# DAC_AFE.net
KiCad netlist of a schematic drawn in Altium Designer
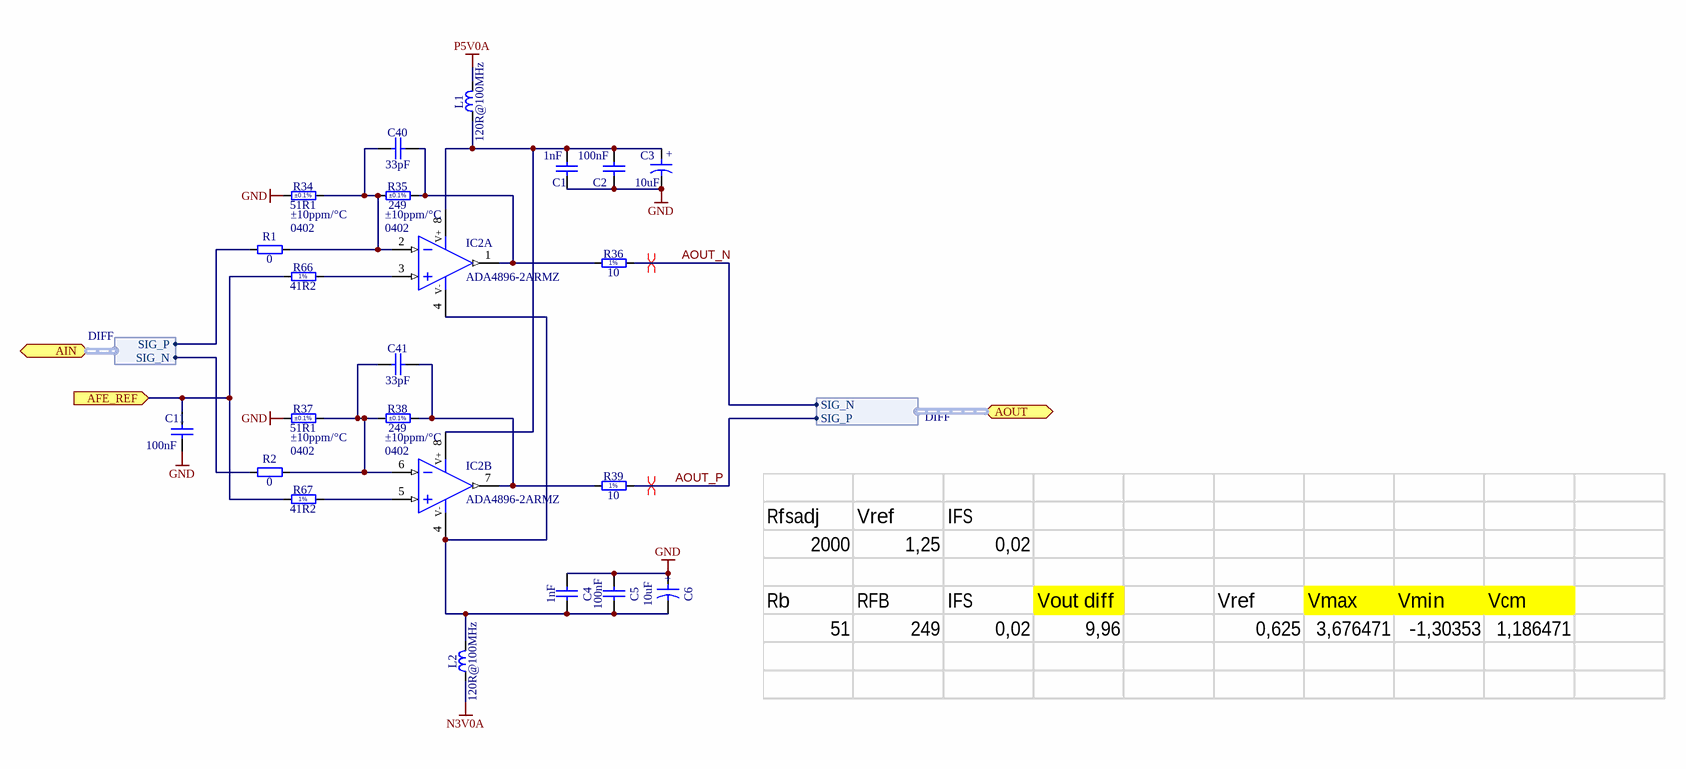
[diagram p0: DAC_AFE.SchDoc]

(export (version "E")
  (design (tool "Eeschema 10.0.6"))
  (components
    (comp (ref "C1")
      (value "1nF")
      (footprint "CAPC0603X33N")
      (description "Non-polarised capacitor")
      (fields
        (field (name "PART NUMBER") "CC0201_1NF_16V_10%_X5R")
        (field (name "VOLTAGE") "16V")
        (field (name "AUTHOR") "CERN DEM JLC")
      )
      (libsource (lib "Capacitors") (part "Capacitor - non polarized"))
    )
    (comp (ref "C2")
      (value "100nF")
      (footprint "CAPC0603X33N")
      (description "Non-polarised capacitor")
      (fields
        (field (name "PART NUMBER") "CC0201_100NF_6.3V_10%_X5R")
        (field (name "VOLTAGE") "6.3V")
        (field (name "AUTHOR") "CERN DEM JLC")
      )
      (libsource (lib "Capacitors") (part "Capacitor - non polarized"))
    )
    (comp (ref "C3")
      (value "10uF")
      (footprint "CAPMP3216X180N")
      (description "Polarised capacitor")
      (fields
        (field (name "PART NUMBER") "CTE3216-18_10UF_10V_10%_LESR1800")
        (field (name "VOLTAGE") "10V")
        (field (name "AUTHOR") "CERN DEM JLC")
      )
      (libsource (lib "Capacitors") (part "Capacitor - polarized"))
    )
    (comp (ref "C4")
      (value "1nF")
      (footprint "CAPC0603X33N")
      (description "Non-polarised capacitor")
      (fields
        (field (name "PART NUMBER") "CC0201_1NF_16V_10%_X5R")
        (field (name "VOLTAGE") "16V")
        (field (name "AUTHOR") "CERN DEM JLC")
      )
      (libsource (lib "Capacitors") (part "Capacitor - non polarized"))
    )
    (comp (ref "C5")
      (value "100nF")
      (footprint "CAPC0603X33N")
      (description "Non-polarised capacitor")
      (fields
        (field (name "PART NUMBER") "CC0201_100NF_6.3V_10%_X5R")
        (field (name "VOLTAGE") "6.3V")
        (field (name "AUTHOR") "CERN DEM JLC")
      )
      (libsource (lib "Capacitors") (part "Capacitor - non polarized"))
    )
    (comp (ref "C6")
      (value "10uF")
      (footprint "CAPMP3216X180N")
      (description "Polarised capacitor")
      (fields
        (field (name "PART NUMBER") "CTE3216-18_10UF_10V_10%_LESR1800")
        (field (name "VOLTAGE") "10V")
        (field (name "AUTHOR") "CERN DEM JLC")
      )
      (libsource (lib "") (part "Capacitor - polarized_1"))
    )
    (comp (ref "C11")
      (value "100nF")
      (footprint "CAPC0603X33N")
      (description "Non-polarised capacitor")
      (fields
        (field (name "PART NUMBER") "CC0201_100NF_6.3V_10%_X5R")
        (field (name "VOLTAGE") "6.3V")
        (field (name "AUTHOR") "CERN DEM JLC")
      )
      (libsource (lib "Capacitors") (part "Capacitor - non polarized"))
    )
    (comp (ref "C40")
      (value "33pF")
      (footprint "CAPC1005X61N")
      (description "Non-polarised capacitor")
      (fields
        (field (name "PART NUMBER") "CC0402_33PF_50V_1%_NP0_JOHANSON_R07S")
        (field (name "VOLTAGE") "50V")
        (field (name "AUTHOR") "CERN DEM BC")
      )
      (libsource (lib "Capacitors") (part "Capacitor - non polarized"))
    )
    (comp (ref "C41")
      (value "33pF")
      (footprint "CAPC1005X61N")
      (description "Non-polarised capacitor")
      (fields
        (field (name "PART NUMBER") "CC0402_33PF_50V_1%_NP0_JOHANSON_R07S")
        (field (name "VOLTAGE") "50V")
        (field (name "AUTHOR") "CERN DEM BC")
      )
      (libsource (lib "Capacitors") (part "Capacitor - non polarized"))
    )
    (comp (ref "IC2")
      (value "ADA4896-2ARMZ")
      (footprint "SOP65P490X110-8N")
      (description "Dual Operational Amplifier")
      (fields (field (name "MANUFACTURER") "ANALOG DEVICES") (field (name "AUTHOR") "CERN DEM MR"))
      (libsource (lib "ICs And Semiconductors") (part "Operational Amplifier x2 Type1"))
    )
    (comp (ref "L1")
      (value "120R@100MHz")
      (footprint "INDC1608X95N")
      (description "Inductor")
      (fields
        (field (name "PART NUMBER") "IND0603_MURATA_BLM18PG121SN1D")
        (field (name "POWER") "2A")
        (field (name "AUTHOR") "CERN DEM BC")
      )
      (libsource (lib "Inductors & Transformers") (part "Inductor"))
    )
    (comp (ref "L2")
      (value "120R@100MHz")
      (footprint "INDC1608X95N")
      (description "Inductor")
      (fields
        (field (name "PART NUMBER") "IND0603_MURATA_BLM18PG121SN1D")
        (field (name "POWER") "2A")
        (field (name "AUTHOR") "CERN DEM BC")
      )
      (libsource (lib "Inductors & Transformers") (part "Inductor"))
    )
    (comp (ref "R1")
      (value "0")
      (footprint "RESC0603X28N")
      (description "Resistor")
      (fields
        (field (name "PART NUMBER") "R0201_0R_JUMPER")
        (field (name "MANUFACTURER") "GENERIC")
        (field (name "AUTHOR") "CERN DEM JLC")
      )
      (libsource (lib "Resistors") (part "Resistor"))
    )
    (comp (ref "R2")
      (value "0")
      (footprint "RESC0603X28N")
      (description "Resistor")
      (fields
        (field (name "PART NUMBER") "R0201_0R_JUMPER")
        (field (name "MANUFACTURER") "GENERIC")
        (field (name "AUTHOR") "CERN DEM JLC")
      )
      (libsource (lib "Resistors") (part "Resistor"))
    )
    (comp (ref "R34")
      (value "51R1")
      (footprint "RESC1005X35N")
      (description "Resistor - 0.1%")
      (fields
        (field (name "PART NUMBER") "R_0402_51R1_0.1%_10ppm")
        (field (name "POWER") "1/16W")
        (field (name "TC") "±10ppm/°C")
        (field (name "CASE") "0402")
        (field (name "TOLERANCE") "±0.1%")
        (field (name "AUTHOR") "GK")
      )
      (libsource (lib "Passives_RC") (part "RES_0402_51R1_0.1%_10ppm"))
    )
    (comp (ref "R35")
      (value "249")
      (footprint "RESC1005X35N")
      (description "Resistor - 0.1%")
      (fields
        (field (name "PART NUMBER") "R_0402_249R_0.1%_10ppm")
        (field (name "POWER") "1/16W")
        (field (name "TC") "±10ppm/°C")
        (field (name "CASE") "0402")
        (field (name "TOLERANCE") "±0.1%")
        (field (name "AUTHOR") "GK")
      )
      (libsource (lib "Passives_RC") (part "RES_0402_249R_0.1%_10ppm"))
    )
    (comp (ref "R36")
      (value "10")
      (footprint "RESC1005X40N")
      (description "Resistor - 1%")
      (fields
        (field (name "PART NUMBER") "R0402_10R_1%_0.0625W_200PPM")
        (field (name "POWER") "0.0625W")
        (field (name "AUTHOR") "CERN DEM JLC")
      )
      (libsource (lib "Resistors") (part "Resistor - 1%"))
    )
    (comp (ref "R37")
      (value "51R1")
      (footprint "RESC1005X35N")
      (description "Resistor - 0.1%")
      (fields
        (field (name "PART NUMBER") "R_0402_51R1_0.1%_10ppm")
        (field (name "POWER") "1/16W")
        (field (name "TC") "±10ppm/°C")
        (field (name "CASE") "0402")
        (field (name "TOLERANCE") "±0.1%")
        (field (name "AUTHOR") "GK")
      )
      (libsource (lib "Passives_RC") (part "RES_0402_51R1_0.1%_10ppm"))
    )
    (comp (ref "R38")
      (value "249")
      (footprint "RESC1005X35N")
      (description "Resistor - 0.1%")
      (fields
        (field (name "PART NUMBER") "R_0402_249R_0.1%_10ppm")
        (field (name "POWER") "1/16W")
        (field (name "TC") "±10ppm/°C")
        (field (name "CASE") "0402")
        (field (name "TOLERANCE") "±0.1%")
        (field (name "AUTHOR") "GK")
      )
      (libsource (lib "Passives_RC") (part "RES_0402_249R_0.1%_10ppm"))
    )
    (comp (ref "R39")
      (value "10")
      (footprint "RESC1005X40N")
      (description "Resistor - 1%")
      (fields
        (field (name "PART NUMBER") "R0402_10R_1%_0.0625W_200PPM")
        (field (name "POWER") "0.0625W")
        (field (name "AUTHOR") "CERN DEM JLC")
      )
      (libsource (lib "Resistors") (part "Resistor - 1%"))
    )
    (comp (ref "R66")
      (value "41R2")
      (footprint "RESC0603X28N")
      (description "41R2k, 0201, 1%")
      (fields
        (field (name "PART NUMBER") "R0201_41R2_1%_200ppm")
        (field (name "POWER") "0.05W")
        (field (name "AUTHOR") "GK")
      )
      (libsource (lib "Passives_RC") (part "RES_0201_41R2_1%_200ppm"))
    )
    (comp (ref "R67")
      (value "41R2")
      (footprint "RESC0603X28N")
      (description "41R2k, 0201, 1%")
      (fields
        (field (name "PART NUMBER") "R0201_41R2_1%_200ppm")
        (field (name "POWER") "0.05W")
        (field (name "AUTHOR") "GK")
      )
      (libsource (lib "Passives_RC") (part "RES_0201_41R2_1%_200ppm"))
    )
  )
  (nets
    (net (code "2") (name "/AFE_REF") (class "Default")
      (node (ref "C11") (pin "1") (pinfunction "1_1") (pintype "passive"))
      (node (ref "R66") (pin "1") (pinfunction "1_1") (pintype "passive"))
      (node (ref "R67") (pin "1") (pinfunction "1_1") (pintype "passive"))
    )
    (net (code "3") (name "/AOUT_N") (class "Default")
      (node (ref "R36") (pin "2") (pinfunction "2_2") (pintype "passive"))
    )
    (net (code "4") (name "/AOUT_P") (class "Default")
      (node (ref "R39") (pin "2") (pinfunction "2_2") (pintype "passive"))
    )
    (net (code "6") (name "GND") (class "Default")
      (node (ref "C1") (pin "2") (pinfunction "2_2") (pintype "passive"))
      (node (ref "C11") (pin "2") (pinfunction "2_2") (pintype "passive"))
      (node (ref "C2") (pin "2") (pinfunction "2_2") (pintype "passive"))
      (node (ref "C3") (pin "2") (pinfunction "2_2") (pintype "passive"))
      (node (ref "C4") (pin "2") (pinfunction "2_2") (pintype "passive"))
      (node (ref "C5") (pin "2") (pinfunction "2_2") (pintype "passive"))
      (node (ref "C6") (pin "1") (pinfunction "1_1") (pintype "passive"))
      (node (ref "R34") (pin "1") (pinfunction "1_1") (pintype "passive"))
      (node (ref "R37") (pin "1") (pinfunction "1_1") (pintype "passive"))
    )
    (net (code "7") (name "N3V0A") (class "Default")
      (node (ref "L2") (pin "1") (pinfunction "1_1") (pintype "passive"))
    )
    (net (code "8") (name "Net-(IC2A-IN+)") (class "Default")
      (node (ref "IC2") (pin "3") (pinfunction "IN+_3") (pintype "input"))
      (node (ref "R66") (pin "2") (pinfunction "2_2") (pintype "passive"))
    )
    (net (code "9") (name "Net-(IC2A-IN-)") (class "Default")
      (node (ref "C40") (pin "1") (pinfunction "1_1") (pintype "passive"))
      (node (ref "IC2") (pin "2") (pinfunction "IN-_2") (pintype "input"))
      (node (ref "R1") (pin "2") (pinfunction "2_2") (pintype "passive"))
      (node (ref "R34") (pin "2") (pinfunction "2_2") (pintype "passive"))
      (node (ref "R35") (pin "1") (pinfunction "1_1") (pintype "passive"))
    )
    (net (code "10") (name "Net-(IC2A-OUT)") (class "Default")
      (node (ref "C40") (pin "2") (pinfunction "2_2") (pintype "passive"))
      (node (ref "IC2") (pin "1") (pinfunction "OUT_1") (pintype "output"))
      (node (ref "R35") (pin "2") (pinfunction "2_2") (pintype "passive"))
      (node (ref "R36") (pin "1") (pinfunction "1_1") (pintype "passive"))
    )
    (net (code "11") (name "Net-(IC2A-V+)") (class "Default")
      (node (ref "C1") (pin "1") (pinfunction "1_1") (pintype "passive"))
      (node (ref "C2") (pin "1") (pinfunction "1_1") (pintype "passive"))
      (node (ref "C3") (pin "1") (pinfunction "1_1") (pintype "passive"))
      (node (ref "IC2") (pin "8") (pinfunction "V+_8") (pintype "power_in"))
      (node (ref "L1") (pin "1") (pinfunction "1_1") (pintype "passive"))
    )
    (net (code "12") (name "Net-(IC2A-V-)") (class "Default")
      (node (ref "C4") (pin "1") (pinfunction "1_1") (pintype "passive"))
      (node (ref "C5") (pin "1") (pinfunction "1_1") (pintype "passive"))
      (node (ref "C6") (pin "2") (pinfunction "2_2") (pintype "passive"))
      (node (ref "IC2") (pin "4") (pinfunction "V-_4") (pintype "power_in"))
      (node (ref "L2") (pin "2") (pinfunction "2_2") (pintype "passive"))
    )
    (net (code "13") (name "Net-(IC2B-IN+)") (class "Default")
      (node (ref "IC2") (pin "5") (pinfunction "IN+_5") (pintype "input"))
      (node (ref "R67") (pin "2") (pinfunction "2_2") (pintype "passive"))
    )
    (net (code "14") (name "Net-(IC2B-IN-)") (class "Default")
      (node (ref "C41") (pin "1") (pinfunction "1_1") (pintype "passive"))
      (node (ref "IC2") (pin "6") (pinfunction "IN-_6") (pintype "input"))
      (node (ref "R2") (pin "2") (pinfunction "2_2") (pintype "passive"))
      (node (ref "R37") (pin "2") (pinfunction "2_2") (pintype "passive"))
      (node (ref "R38") (pin "1") (pinfunction "1_1") (pintype "passive"))
    )
    (net (code "15") (name "Net-(IC2B-OUT)") (class "Default")
      (node (ref "C41") (pin "2") (pinfunction "2_2") (pintype "passive"))
      (node (ref "IC2") (pin "7") (pinfunction "OUT_7") (pintype "output"))
      (node (ref "R38") (pin "2") (pinfunction "2_2") (pintype "passive"))
      (node (ref "R39") (pin "1") (pinfunction "1_1") (pintype "passive"))
    )
    (net (code "16") (name "P5V0A") (class "Default")
      (node (ref "L1") (pin "2") (pinfunction "2_2") (pintype "passive"))
    )
    (net (code "17") (name "unconnected-(R1-Pad1)") (class "Default")
      (node (ref "R1") (pin "1") (pinfunction "1_1") (pintype "passive"))
    )
    (net (code "18") (name "unconnected-(R2-Pad1)") (class "Default")
      (node (ref "R2") (pin "1") (pinfunction "1_1") (pintype "passive"))
    )
  )
)
